# Mezclador1.net
KiCad netlist of a schematic drawn in Altium Designer
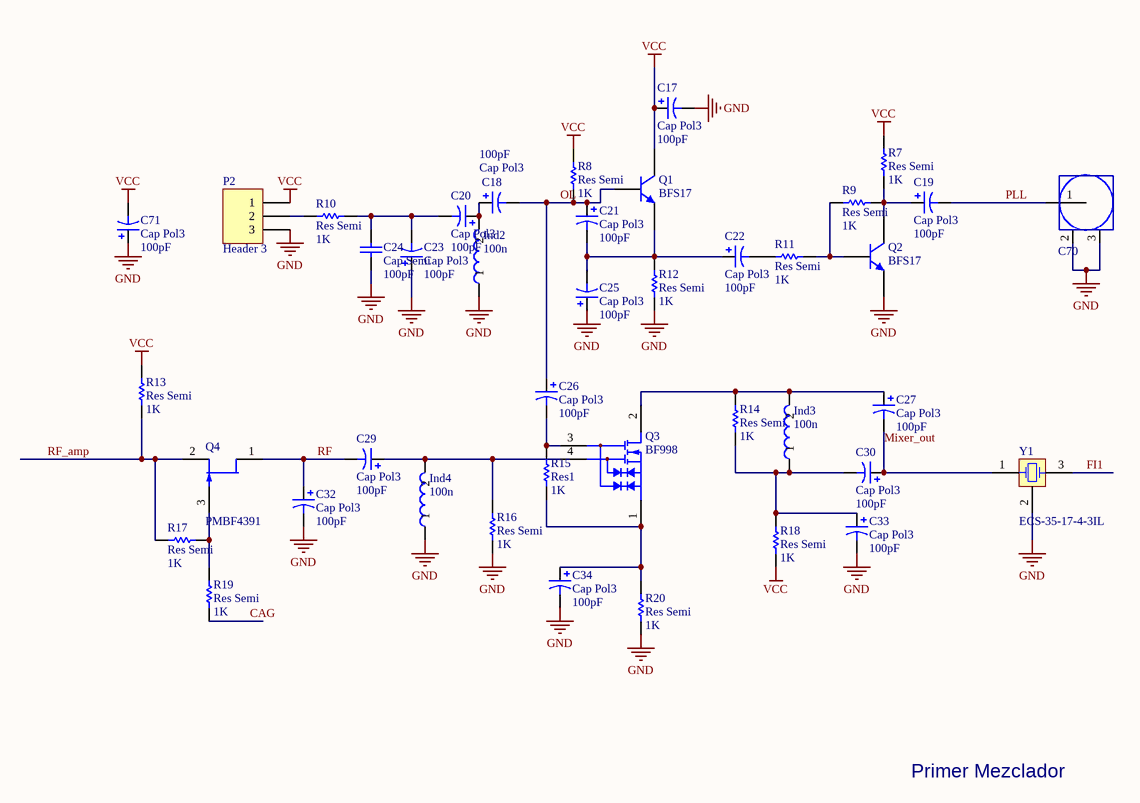
[diagram p0: Mezclador1.SchDoc]

(export (version "E")
  (design (tool "Eeschema 10.0.6"))
  (components
    (comp (ref "C17")
      (value "Cap Pol3")
      (footprint "C0805")
      (description "Polarized Capacitor (Surface Mount)")
      (fields (field (name "ALTIUM_VALUE") "100pF") (field (name "PUBLISHER") "Altium Limited"))
      (libsource (lib "Miscellaneous Devices") (part "Cap Pol3"))
    )
    (comp (ref "C18")
      (value "Cap Pol3")
      (footprint "C0805")
      (description "Polarized Capacitor (Surface Mount)")
      (fields (field (name "ALTIUM_VALUE") "100pF") (field (name "PUBLISHER") "Altium Limited"))
      (libsource (lib "Miscellaneous Devices") (part "Cap Pol3"))
    )
    (comp (ref "C19")
      (value "Cap Pol3")
      (footprint "C0805")
      (description "Polarized Capacitor (Surface Mount)")
      (fields (field (name "ALTIUM_VALUE") "100pF") (field (name "PUBLISHER") "Altium Limited"))
      (libsource (lib "Miscellaneous Devices") (part "Cap Pol3"))
    )
    (comp (ref "C20")
      (value "Cap Pol3")
      (footprint "C0805")
      (description "Polarized Capacitor (Surface Mount)")
      (fields (field (name "ALTIUM_VALUE") "100pF") (field (name "PUBLISHER") "Altium Limited"))
      (libsource (lib "Miscellaneous Devices") (part "Cap Pol3"))
    )
    (comp (ref "C21")
      (value "Cap Pol3")
      (footprint "C0805")
      (description "Polarized Capacitor (Surface Mount)")
      (fields (field (name "ALTIUM_VALUE") "100pF") (field (name "PUBLISHER") "Altium Limited"))
      (libsource (lib "Miscellaneous Devices") (part "Cap Pol3"))
    )
    (comp (ref "C22")
      (value "Cap Pol3")
      (footprint "C0805")
      (description "Polarized Capacitor (Surface Mount)")
      (fields (field (name "ALTIUM_VALUE") "100pF") (field (name "PUBLISHER") "Altium Limited"))
      (libsource (lib "Miscellaneous Devices") (part "Cap Pol3"))
    )
    (comp (ref "C23")
      (value "Cap Pol3")
      (footprint "C0805")
      (description "Polarized Capacitor (Surface Mount)")
      (fields (field (name "ALTIUM_VALUE") "100pF") (field (name "PUBLISHER") "Altium Limited"))
      (libsource (lib "Miscellaneous Devices") (part "Cap Pol3"))
    )
    (comp (ref "C24")
      (value "Cap Semi")
      (footprint "C1206")
      (description "Capacitor (Semiconductor SIM Model)")
      (fields (field (name "ALTIUM_VALUE") "100pF") (field (name "PUBLISHER") "Altium Limited"))
      (libsource (lib "Miscellaneous Devices") (part "Cap Semi"))
    )
    (comp (ref "C25")
      (value "Cap Pol3")
      (footprint "C0805")
      (description "Polarized Capacitor (Surface Mount)")
      (fields (field (name "ALTIUM_VALUE") "100pF") (field (name "PUBLISHER") "Altium Limited"))
      (libsource (lib "Miscellaneous Devices") (part "Cap Pol3"))
    )
    (comp (ref "C26")
      (value "Cap Pol3")
      (footprint "C0805")
      (description "Polarized Capacitor (Surface Mount)")
      (fields (field (name "ALTIUM_VALUE") "100pF") (field (name "PUBLISHER") "Altium Limited"))
      (libsource (lib "Miscellaneous Devices") (part "Cap Pol3"))
    )
    (comp (ref "C27")
      (value "Cap Pol3")
      (footprint "C0805")
      (description "Polarized Capacitor (Surface Mount)")
      (fields (field (name "ALTIUM_VALUE") "100pF") (field (name "PUBLISHER") "Altium Limited"))
      (libsource (lib "Miscellaneous Devices") (part "Cap Pol3"))
    )
    (comp (ref "C29")
      (value "Cap Pol3")
      (footprint "C0805")
      (description "Polarized Capacitor (Surface Mount)")
      (fields (field (name "ALTIUM_VALUE") "100pF") (field (name "PUBLISHER") "Altium Limited"))
      (libsource (lib "Miscellaneous Devices") (part "Cap Pol3"))
    )
    (comp (ref "C30")
      (value "Cap Pol3")
      (footprint "C0805")
      (description "Polarized Capacitor (Surface Mount)")
      (fields (field (name "ALTIUM_VALUE") "100pF") (field (name "PUBLISHER") "Altium Limited"))
      (libsource (lib "Miscellaneous Devices") (part "Cap Pol3"))
    )
    (comp (ref "C32")
      (value "Cap Pol3")
      (footprint "C0805")
      (description "Polarized Capacitor (Surface Mount)")
      (fields (field (name "ALTIUM_VALUE") "100pF") (field (name "PUBLISHER") "Altium Limited"))
      (libsource (lib "Miscellaneous Devices") (part "Cap Pol3"))
    )
    (comp (ref "C33")
      (value "Cap Pol3")
      (footprint "C0805")
      (description "Polarized Capacitor (Surface Mount)")
      (fields (field (name "ALTIUM_VALUE") "100pF") (field (name "PUBLISHER") "Altium Limited"))
      (libsource (lib "Miscellaneous Devices") (part "Cap Pol3"))
    )
    (comp (ref "C34")
      (value "Cap Pol3")
      (footprint "C0805")
      (description "Polarized Capacitor (Surface Mount)")
      (fields (field (name "ALTIUM_VALUE") "100pF") (field (name "PUBLISHER") "Altium Limited"))
      (libsource (lib "Miscellaneous Devices") (part "Cap Pol3"))
    )
    (comp (ref "C70") (value "SMA_2") (footprint "SMA-2holeD") (libsource (lib "epf") (part "SMA_2")))
    (comp (ref "C71")
      (value "Cap Pol3")
      (footprint "C0805")
      (description "Polarized Capacitor (Surface Mount)")
      (fields (field (name "ALTIUM_VALUE") "100pF") (field (name "PUBLISHER") "Altium Limited"))
      (libsource (lib "Miscellaneous Devices") (part "Cap Pol3"))
    )
    (comp (ref "Ind2")
      (value "Ind2")
      (footprint "Ind_4mm")
      (fields (field (name "VALOR") "100n"))
      (libsource (lib "epf") (part "Ind2"))
    )
    (comp (ref "Ind3")
      (value "Ind2")
      (footprint "AXIAL-0.3")
      (fields (field (name "VALOR") "100n"))
      (libsource (lib "epf") (part "Ind2"))
    )
    (comp (ref "Ind4")
      (value "Ind2")
      (footprint "Ind_3mm")
      (fields (field (name "VALOR") "100n"))
      (libsource (lib "epf") (part "Ind2"))
    )
    (comp (ref "P2")
      (value "Header 3")
      (footprint "HDR1X3")
      (description "Header, 3-Pin")
      (fields (field (name "PUBLISHER") "Altium Limited"))
      (libsource (lib "Miscellaneous Connectors") (part "Header 3"))
    )
    (comp (ref "Q1")
      (value "BFS17")
      (footprint "SOT-23")
      (description "NPN 1 GHz Wideband Transistor")
      (fields (field (name "PUBLISHER") "Altium Limited"))
      (libsource (lib "Philips Discrete BJT - RF Transistor") (part "BFS17"))
    )
    (comp (ref "Q2")
      (value "BFS17")
      (footprint "SOT23_N")
      (description "NPN 1 GHz Wideband Transistor")
      (fields (field (name "PUBLISHER") "Altium Limited"))
      (libsource (lib "Philips Discrete BJT - RF Transistor") (part "BFS17"))
    )
    (comp (ref "Q3")
      (value "BF998")
      (footprint "SOT-143")
      (description "Silicon N-channel Dual-gate MOSFET")
      (fields (field (name "PUBLISHER") "Altium Limited"))
      (libsource (lib "Philips Discrete MOSFET - Low Power") (part "BF998"))
    )
    (comp (ref "Q4")
      (value "PMBF4391")
      (footprint "SOT-23")
      (description "N-channel Silicon Junction Field-effect Transistor")
      (fields (field (name "PUBLISHER") "Altium Limited"))
      (libsource (lib "Philips Discrete JFET") (part "PMBF4391"))
    )
    (comp (ref "R7")
      (value "Res Semi")
      (footprint "2012[0805]")
      (description "Semiconductor Resistor")
      (fields (field (name "ALTIUM_VALUE") "1K") (field (name "PUBLISHER") "Altium Limited"))
      (libsource (lib "Miscellaneous Devices") (part "Res Semi"))
    )
    (comp (ref "R8")
      (value "Res Semi")
      (footprint "2012[0805]")
      (description "Semiconductor Resistor")
      (fields (field (name "ALTIUM_VALUE") "1K") (field (name "PUBLISHER") "Altium Limited"))
      (libsource (lib "Miscellaneous Devices") (part "Res Semi"))
    )
    (comp (ref "R9")
      (value "Res Semi")
      (footprint "2012[0805]")
      (description "Semiconductor Resistor")
      (fields (field (name "ALTIUM_VALUE") "1K") (field (name "PUBLISHER") "Altium Limited"))
      (libsource (lib "Miscellaneous Devices") (part "Res Semi"))
    )
    (comp (ref "R10")
      (value "Res Semi")
      (footprint "2012[0805]")
      (description "Semiconductor Resistor")
      (fields (field (name "ALTIUM_VALUE") "1K") (field (name "PUBLISHER") "Altium Limited"))
      (libsource (lib "Miscellaneous Devices") (part "Res Semi"))
    )
    (comp (ref "R11")
      (value "Res Semi")
      (footprint "2012[0805]")
      (description "Semiconductor Resistor")
      (fields (field (name "ALTIUM_VALUE") "1K") (field (name "PUBLISHER") "Altium Limited"))
      (libsource (lib "Miscellaneous Devices") (part "Res Semi"))
    )
    (comp (ref "R12")
      (value "Res Semi")
      (footprint "2012[0805]")
      (description "Semiconductor Resistor")
      (fields (field (name "ALTIUM_VALUE") "1K") (field (name "PUBLISHER") "Altium Limited"))
      (libsource (lib "Miscellaneous Devices") (part "Res Semi"))
    )
    (comp (ref "R13")
      (value "Res Semi")
      (footprint "2012[0805]")
      (description "Semiconductor Resistor")
      (fields (field (name "ALTIUM_VALUE") "1K") (field (name "PUBLISHER") "Altium Limited"))
      (libsource (lib "Miscellaneous Devices") (part "Res Semi"))
    )
    (comp (ref "R14")
      (value "Res Semi")
      (footprint "2012[0805]")
      (description "Semiconductor Resistor")
      (fields (field (name "ALTIUM_VALUE") "1K") (field (name "PUBLISHER") "Altium Limited"))
      (libsource (lib "Miscellaneous Devices") (part "Res Semi"))
    )
    (comp (ref "R15")
      (value "Res1")
      (footprint "AXIAL-0.3")
      (description "Resistor")
      (fields (field (name "ALTIUM_VALUE") "1K") (field (name "PUBLISHER") "Altium Limited"))
      (libsource (lib "Miscellaneous Devices") (part "Res1"))
    )
    (comp (ref "R16")
      (value "Res Semi")
      (footprint "2012[0805]")
      (description "Semiconductor Resistor")
      (fields (field (name "ALTIUM_VALUE") "1K") (field (name "PUBLISHER") "Altium Limited"))
      (libsource (lib "Miscellaneous Devices") (part "Res Semi"))
    )
    (comp (ref "R17")
      (value "Res Semi")
      (footprint "2012[0805]")
      (description "Semiconductor Resistor")
      (fields (field (name "ALTIUM_VALUE") "1K") (field (name "PUBLISHER") "Altium Limited"))
      (libsource (lib "Miscellaneous Devices") (part "Res Semi"))
    )
    (comp (ref "R18")
      (value "Res Semi")
      (footprint "2012[0805]")
      (description "Semiconductor Resistor")
      (fields (field (name "ALTIUM_VALUE") "1K") (field (name "PUBLISHER") "Altium Limited"))
      (libsource (lib "Miscellaneous Devices") (part "Res Semi"))
    )
    (comp (ref "R19")
      (value "Res Semi")
      (footprint "2012[0805]")
      (description "Semiconductor Resistor")
      (fields (field (name "ALTIUM_VALUE") "1K") (field (name "PUBLISHER") "Altium Limited"))
      (libsource (lib "Miscellaneous Devices") (part "Res Semi"))
    )
    (comp (ref "R20")
      (value "Res Semi")
      (footprint "2012[0805]")
      (description "Semiconductor Resistor")
      (fields (field (name "ALTIUM_VALUE") "1K") (field (name "PUBLISHER") "Altium Limited"))
      (libsource (lib "Miscellaneous Devices") (part "Res Semi"))
    )
    (comp (ref "Y1")
      (value "ECS-35-17-4-3IL")
      (footprint "HC-49US")
      (description "Crystal Oscillator, 3rd In-Line Lead Version")
      (fields (field (name "PUBLISHER") "Altium Limited"))
      (libsource (lib "ECS Crystal Oscillator") (part "ECS-35-17-4-3IL"))
    )
  )
  (nets
    (net (code "1") (name "/CAG") (class "Default")
      (node (ref "R19") (pin "2") (pinfunction "2_2") (pintype "passive"))
    )
    (net (code "2") (name "/FI1") (class "Default")
      (node (ref "Y1") (pin "3") (pinfunction "OSC2_3") (pintype "passive"))
    )
    (net (code "3") (name "/Mixer_out") (class "Default")
      (node (ref "C27") (pin "2") (pinfunction "2_2") (pintype "passive"))
      (node (ref "C30") (pin "1") (pinfunction "1_1") (pintype "passive"))
      (node (ref "Y1") (pin "1") (pinfunction "OSC1_1") (pintype "passive"))
    )
    (net (code "4") (name "/OL") (class "Default")
      (node (ref "C18") (pin "2") (pinfunction "2_2") (pintype "passive"))
      (node (ref "C21") (pin "1") (pinfunction "1_1") (pintype "passive"))
      (node (ref "C26") (pin "1") (pinfunction "1_1") (pintype "passive"))
      (node (ref "Q1") (pin "1") (pinfunction "B_1") (pintype "passive"))
      (node (ref "R8") (pin "1") (pinfunction "1_1") (pintype "passive"))
    )
    (net (code "5") (name "/PLL") (class "Default")
      (node (ref "C19") (pin "2") (pinfunction "2_2") (pintype "passive"))
      (node (ref "C70") (pin "1") (pinfunction "RF_1") (pintype "passive"))
    )
    (net (code "6") (name "/RF") (class "Default")
      (node (ref "C29") (pin "2") (pinfunction "2_2") (pintype "passive"))
      (node (ref "C32") (pin "1") (pinfunction "1_1") (pintype "passive"))
      (node (ref "Q4") (pin "1") (pinfunction "D_1") (pintype "passive"))
    )
    (net (code "7") (name "/RF_amp") (class "Default")
      (node (ref "Q4") (pin "2") (pinfunction "S_2") (pintype "passive"))
      (node (ref "R13") (pin "1") (pinfunction "1_1") (pintype "passive"))
      (node (ref "R17") (pin "1") (pinfunction "1_1") (pintype "passive"))
    )
    (net (code "8") (name "GND") (class "Default")
      (node (ref "C17") (pin "2") (pinfunction "2_2") (pintype "passive"))
      (node (ref "C23") (pin "1") (pinfunction "1_1") (pintype "passive"))
      (node (ref "C24") (pin "2") (pinfunction "2_2") (pintype "passive"))
      (node (ref "C25") (pin "1") (pinfunction "1_1") (pintype "passive"))
      (node (ref "C32") (pin "2") (pinfunction "2_2") (pintype "passive"))
      (node (ref "C33") (pin "2") (pinfunction "2_2") (pintype "passive"))
      (node (ref "C34") (pin "2") (pinfunction "2_2") (pintype "passive"))
      (node (ref "C70") (pin "2") (pinfunction "GND_2") (pintype "passive"))
      (node (ref "C70") (pin "3") (pinfunction "GND_3") (pintype "passive"))
      (node (ref "C71") (pin "1") (pinfunction "1_1") (pintype "passive"))
      (node (ref "Ind2") (pin "1") (pinfunction "1_1") (pintype "passive"))
      (node (ref "Ind4") (pin "1") (pinfunction "1_1") (pintype "passive"))
      (node (ref "P2") (pin "3") (pinfunction "3_3") (pintype "passive"))
      (node (ref "Q2") (pin "2") (pinfunction "E_2") (pintype "passive"))
      (node (ref "R12") (pin "1") (pinfunction "1_1") (pintype "passive"))
      (node (ref "R16") (pin "1") (pinfunction "1_1") (pintype "passive"))
      (node (ref "R20") (pin "1") (pinfunction "1_1") (pintype "passive"))
      (node (ref "Y1") (pin "2") (pinfunction "COM_2") (pintype "passive"))
    )
    (net (code "9") (name "Net-(C18-Pad1)") (class "Default")
      (node (ref "C18") (pin "1") (pinfunction "1_1") (pintype "passive"))
      (node (ref "C20") (pin "1") (pinfunction "1_1") (pintype "passive"))
      (node (ref "Ind2") (pin "2") (pinfunction "2_2") (pintype "passive"))
    )
    (net (code "10") (name "Net-(C20-Pad2)") (class "Default")
      (node (ref "C20") (pin "2") (pinfunction "2_2") (pintype "passive"))
      (node (ref "C23") (pin "2") (pinfunction "2_2") (pintype "passive"))
      (node (ref "C24") (pin "1") (pinfunction "1_1") (pintype "passive"))
      (node (ref "R10") (pin "2") (pinfunction "2_2") (pintype "passive"))
    )
    (net (code "11") (name "Net-(C22-Pad2)") (class "Default")
      (node (ref "C22") (pin "2") (pinfunction "2_2") (pintype "passive"))
      (node (ref "R11") (pin "2") (pinfunction "2_2") (pintype "passive"))
    )
    (net (code "12") (name "Net-(C30-Pad2)") (class "Default")
      (node (ref "C30") (pin "2") (pinfunction "2_2") (pintype "passive"))
      (node (ref "C33") (pin "1") (pinfunction "1_1") (pintype "passive"))
      (node (ref "Ind3") (pin "1") (pinfunction "1_1") (pintype "passive"))
      (node (ref "R14") (pin "1") (pinfunction "1_1") (pintype "passive"))
      (node (ref "R18") (pin "2") (pinfunction "2_2") (pintype "passive"))
    )
    (net (code "13") (name "Net-(P2-Pad2)") (class "Default")
      (node (ref "P2") (pin "2") (pinfunction "2_2") (pintype "passive"))
      (node (ref "R10") (pin "1") (pinfunction "1_1") (pintype "passive"))
    )
    (net (code "14") (name "Net-(Q1-E)") (class "Default")
      (node (ref "C21") (pin "2") (pinfunction "2_2") (pintype "passive"))
      (node (ref "C22") (pin "1") (pinfunction "1_1") (pintype "passive"))
      (node (ref "C25") (pin "2") (pinfunction "2_2") (pintype "passive"))
      (node (ref "Q1") (pin "2") (pinfunction "E_2") (pintype "passive"))
      (node (ref "R12") (pin "2") (pinfunction "2_2") (pintype "passive"))
    )
    (net (code "15") (name "Net-(Q2-B)") (class "Default")
      (node (ref "Q2") (pin "1") (pinfunction "B_1") (pintype "passive"))
      (node (ref "R11") (pin "1") (pinfunction "1_1") (pintype "passive"))
      (node (ref "R9") (pin "2") (pinfunction "2_2") (pintype "passive"))
    )
    (net (code "16") (name "Net-(Q2-C)") (class "Default")
      (node (ref "C19") (pin "1") (pinfunction "1_1") (pintype "passive"))
      (node (ref "Q2") (pin "3") (pinfunction "C_3") (pintype "passive"))
      (node (ref "R7") (pin "2") (pinfunction "2_2") (pintype "passive"))
      (node (ref "R9") (pin "1") (pinfunction "1_1") (pintype "passive"))
    )
    (net (code "17") (name "Net-(Q3-D)") (class "Default")
      (node (ref "C27") (pin "1") (pinfunction "1_1") (pintype "passive"))
      (node (ref "Ind3") (pin "2") (pinfunction "2_2") (pintype "passive"))
      (node (ref "Q3") (pin "2") (pinfunction "D_2") (pintype "passive"))
      (node (ref "R14") (pin "2") (pinfunction "2_2") (pintype "passive"))
    )
    (net (code "18") (name "Net-(Q3-G1)") (class "Default")
      (node (ref "C29") (pin "1") (pinfunction "1_1") (pintype "passive"))
      (node (ref "Ind4") (pin "2") (pinfunction "2_2") (pintype "passive"))
      (node (ref "Q3") (pin "4") (pinfunction "G1_4") (pintype "passive"))
      (node (ref "R16") (pin "2") (pinfunction "2_2") (pintype "passive"))
    )
    (net (code "19") (name "Net-(Q3-G2)") (class "Default")
      (node (ref "C26") (pin "2") (pinfunction "2_2") (pintype "passive"))
      (node (ref "Q3") (pin "3") (pinfunction "G2_3") (pintype "passive"))
      (node (ref "R15") (pin "2") (pinfunction "2_2") (pintype "passive"))
    )
    (net (code "20") (name "Net-(Q3-S)") (class "Default")
      (node (ref "C34") (pin "1") (pinfunction "1_1") (pintype "passive"))
      (node (ref "Q3") (pin "1") (pinfunction "S_1") (pintype "passive"))
      (node (ref "R15") (pin "1") (pinfunction "1_1") (pintype "passive"))
      (node (ref "R20") (pin "2") (pinfunction "2_2") (pintype "passive"))
    )
    (net (code "21") (name "Net-(Q4-G)") (class "Default")
      (node (ref "Q4") (pin "3") (pinfunction "G_3") (pintype "passive"))
      (node (ref "R17") (pin "2") (pinfunction "2_2") (pintype "passive"))
      (node (ref "R19") (pin "1") (pinfunction "1_1") (pintype "passive"))
    )
    (net (code "22") (name "VCC") (class "Default")
      (node (ref "C17") (pin "1") (pinfunction "1_1") (pintype "passive"))
      (node (ref "C71") (pin "2") (pinfunction "2_2") (pintype "passive"))
      (node (ref "P2") (pin "1") (pinfunction "1_1") (pintype "passive"))
      (node (ref "Q1") (pin "3") (pinfunction "C_3") (pintype "passive"))
      (node (ref "R13") (pin "2") (pinfunction "2_2") (pintype "passive"))
      (node (ref "R18") (pin "1") (pinfunction "1_1") (pintype "passive"))
      (node (ref "R7") (pin "1") (pinfunction "1_1") (pintype "passive"))
      (node (ref "R8") (pin "2") (pinfunction "2_2") (pintype "passive"))
    )
  )
)
